# MIPI_x2CSI.net
KiCad netlist of a schematic drawn in Altium Designer
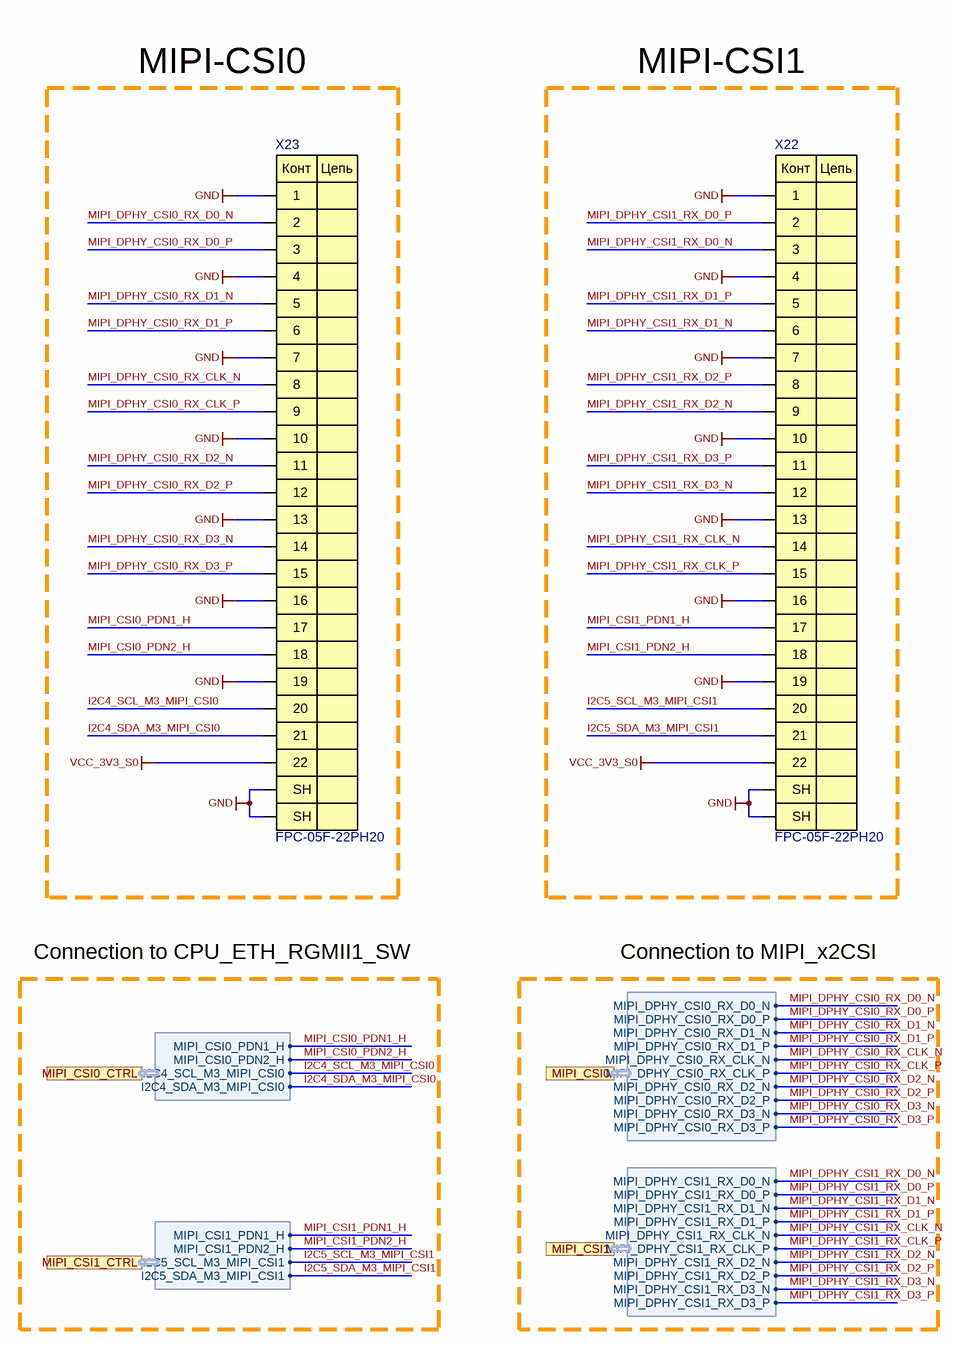
[diagram p0: MIPI_x2CSI.SchDoc]

(export (version "E")
  (design (tool "Eeschema 10.0.6"))
  (components
    (comp (ref "X22")
      (value "FPC-05F-22PH20")
      (footprint "FPC-05F-22PH20")
      (description "FFC/FPC Connector 22 Position 0.5mm Pitch Bottom Contact Surface Mount, Right Angle -25℃~+85℃")
      (fields (field (name "MANUFACTURER") "XUNPU"))
      (libsource (lib "LIB_RK") (part "FPC-05F-22PH20"))
    )
    (comp (ref "X23")
      (value "FPC-05F-22PH20")
      (footprint "FPC-05F-22PH20")
      (description "FFC/FPC Connector 22 Position 0.5mm Pitch Bottom Contact Surface Mount, Right Angle -25℃~+85℃")
      (fields (field (name "MANUFACTURER") "XUNPU"))
      (libsource (lib "LIB_RK") (part "FPC-05F-22PH20"))
    )
  )
  (nets
    (net (code "5") (name "/I2C4_SCL_M3_MIPI_CSI0") (class "Default")
      (node (ref "X23") (pin "20") (pinfunction "20_20") (pintype "passive"))
    )
    (net (code "6") (name "/I2C4_SDA_M3_MIPI_CSI0") (class "Default")
      (node (ref "X23") (pin "21") (pinfunction "21_21") (pintype "passive"))
    )
    (net (code "7") (name "/I2C5_SCL_M3_MIPI_CSI1") (class "Default")
      (node (ref "X22") (pin "20") (pinfunction "20_20") (pintype "passive"))
    )
    (net (code "8") (name "/I2C5_SDA_M3_MIPI_CSI1") (class "Default")
      (node (ref "X22") (pin "21") (pinfunction "21_21") (pintype "passive"))
    )
    (net (code "9") (name "/MIPI_CSI0_PDN1_H") (class "Default")
      (node (ref "X23") (pin "17") (pinfunction "17_17") (pintype "passive"))
    )
    (net (code "10") (name "/MIPI_CSI0_PDN2_H") (class "Default")
      (node (ref "X23") (pin "18") (pinfunction "18_18") (pintype "passive"))
    )
    (net (code "11") (name "/MIPI_CSI1_PDN1_H") (class "Default")
      (node (ref "X22") (pin "17") (pinfunction "17_17") (pintype "passive"))
    )
    (net (code "12") (name "/MIPI_CSI1_PDN2_H") (class "Default")
      (node (ref "X22") (pin "18") (pinfunction "18_18") (pintype "passive"))
    )
    (net (code "13") (name "/MIPI_DPHY_CSI0_RX_CLK_N") (class "Default")
      (node (ref "X23") (pin "8") (pinfunction "8_8") (pintype "passive"))
    )
    (net (code "14") (name "/MIPI_DPHY_CSI0_RX_CLK_P") (class "Default")
      (node (ref "X23") (pin "9") (pinfunction "9_9") (pintype "passive"))
    )
    (net (code "15") (name "/MIPI_DPHY_CSI0_RX_D0_N") (class "Default")
      (node (ref "X23") (pin "2") (pinfunction "2_2") (pintype "passive"))
    )
    (net (code "16") (name "/MIPI_DPHY_CSI0_RX_D0_P") (class "Default")
      (node (ref "X23") (pin "3") (pinfunction "3_3") (pintype "passive"))
    )
    (net (code "17") (name "/MIPI_DPHY_CSI0_RX_D1_N") (class "Default")
      (node (ref "X23") (pin "5") (pinfunction "5_5") (pintype "passive"))
    )
    (net (code "18") (name "/MIPI_DPHY_CSI0_RX_D1_P") (class "Default")
      (node (ref "X23") (pin "6") (pinfunction "6_6") (pintype "passive"))
    )
    (net (code "19") (name "/MIPI_DPHY_CSI0_RX_D2_N") (class "Default")
      (node (ref "X23") (pin "11") (pinfunction "11_11") (pintype "passive"))
    )
    (net (code "20") (name "/MIPI_DPHY_CSI0_RX_D2_P") (class "Default")
      (node (ref "X23") (pin "12") (pinfunction "12_12") (pintype "passive"))
    )
    (net (code "21") (name "/MIPI_DPHY_CSI0_RX_D3_N") (class "Default")
      (node (ref "X23") (pin "14") (pinfunction "14_14") (pintype "passive"))
    )
    (net (code "22") (name "/MIPI_DPHY_CSI0_RX_D3_P") (class "Default")
      (node (ref "X23") (pin "15") (pinfunction "15_15") (pintype "passive"))
    )
    (net (code "23") (name "/MIPI_DPHY_CSI1_RX_CLK_N") (class "Default")
      (node (ref "X22") (pin "14") (pinfunction "14_14") (pintype "passive"))
    )
    (net (code "24") (name "/MIPI_DPHY_CSI1_RX_CLK_P") (class "Default")
      (node (ref "X22") (pin "15") (pinfunction "15_15") (pintype "passive"))
    )
    (net (code "25") (name "/MIPI_DPHY_CSI1_RX_D0_N") (class "Default")
      (node (ref "X22") (pin "3") (pinfunction "3_3") (pintype "passive"))
    )
    (net (code "26") (name "/MIPI_DPHY_CSI1_RX_D0_P") (class "Default")
      (node (ref "X22") (pin "2") (pinfunction "2_2") (pintype "passive"))
    )
    (net (code "27") (name "/MIPI_DPHY_CSI1_RX_D1_N") (class "Default")
      (node (ref "X22") (pin "6") (pinfunction "6_6") (pintype "passive"))
    )
    (net (code "28") (name "/MIPI_DPHY_CSI1_RX_D1_P") (class "Default")
      (node (ref "X22") (pin "5") (pinfunction "5_5") (pintype "passive"))
    )
    (net (code "29") (name "/MIPI_DPHY_CSI1_RX_D2_N") (class "Default")
      (node (ref "X22") (pin "9") (pinfunction "9_9") (pintype "passive"))
    )
    (net (code "30") (name "/MIPI_DPHY_CSI1_RX_D2_P") (class "Default")
      (node (ref "X22") (pin "8") (pinfunction "8_8") (pintype "passive"))
    )
    (net (code "31") (name "/MIPI_DPHY_CSI1_RX_D3_N") (class "Default")
      (node (ref "X22") (pin "12") (pinfunction "12_12") (pintype "passive"))
    )
    (net (code "32") (name "/MIPI_DPHY_CSI1_RX_D3_P") (class "Default")
      (node (ref "X22") (pin "11") (pinfunction "11_11") (pintype "passive"))
    )
    (net (code "37") (name "GND") (class "Default")
      (node (ref "X22") (pin "1") (pinfunction "1_1") (pintype "passive"))
      (node (ref "X22") (pin "10") (pinfunction "10_10") (pintype "passive"))
      (node (ref "X22") (pin "13") (pinfunction "13_13") (pintype "passive"))
      (node (ref "X22") (pin "16") (pinfunction "16_16") (pintype "passive"))
      (node (ref "X22") (pin "19") (pinfunction "19_19") (pintype "passive"))
      (node (ref "X22") (pin "23") (pinfunction "SH_23") (pintype "passive"))
      (node (ref "X22") (pin "24") (pinfunction "SH_24") (pintype "passive"))
      (node (ref "X22") (pin "4") (pinfunction "4_4") (pintype "passive"))
      (node (ref "X22") (pin "7") (pinfunction "7_7") (pintype "passive"))
      (node (ref "X23") (pin "1") (pinfunction "1_1") (pintype "passive"))
      (node (ref "X23") (pin "10") (pinfunction "10_10") (pintype "passive"))
      (node (ref "X23") (pin "13") (pinfunction "13_13") (pintype "passive"))
      (node (ref "X23") (pin "16") (pinfunction "16_16") (pintype "passive"))
      (node (ref "X23") (pin "19") (pinfunction "19_19") (pintype "passive"))
      (node (ref "X23") (pin "23") (pinfunction "SH_23") (pintype "passive"))
      (node (ref "X23") (pin "24") (pinfunction "SH_24") (pintype "passive"))
      (node (ref "X23") (pin "4") (pinfunction "4_4") (pintype "passive"))
      (node (ref "X23") (pin "7") (pinfunction "7_7") (pintype "passive"))
    )
    (net (code "38") (name "VCC_3V3_S0") (class "Default")
      (node (ref "X22") (pin "22") (pinfunction "22_22") (pintype "passive"))
      (node (ref "X23") (pin "22") (pinfunction "22_22") (pintype "passive"))
    )
  )
)
